# Sheet1.net
KiCad netlist of a schematic drawn in Altium Designer
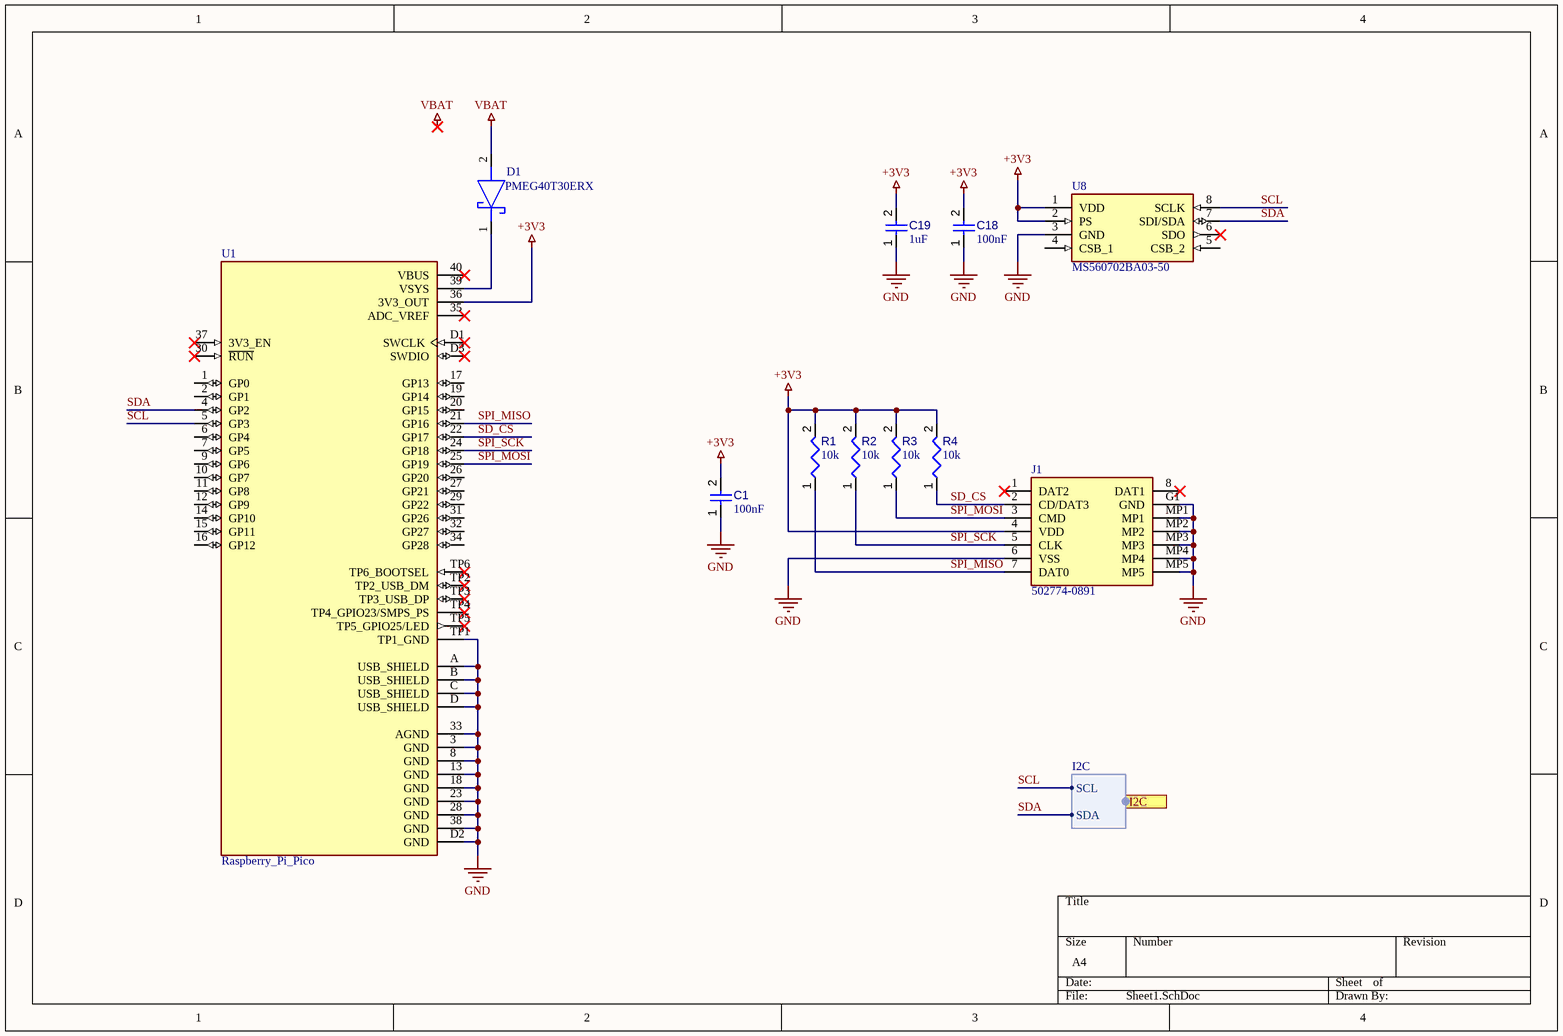
[diagram p0: Sheet1.SchDoc]

(export (version "E")
  (design (tool "Eeschema 10.0.6"))
  (components
    (comp (ref "C1")
      (value "100nF")
      (footprint "CAPC1608X90X40NL10T20")
      (description "Chip Capacitor, 100 nF, +/- 10%, 50 V, 0603 (1608 Metric)")
      (fields (field (name "TOLERANCE") "10%") (field (name "Comment") "Capacitor 100 nF +/-10% 50 V 0603"))
      (libsource (lib "PWr in Space team") (part "CAP-NP-2"))
    )
    (comp (ref "C18")
      (value "100nF")
      (footprint "CAPC1608X90X40NL10T20")
      (description "Chip Capacitor, 100 nF, +/- 10%, 50 V, 0603 (1608 Metric)")
      (fields (field (name "TOLERANCE") "10%") (field (name "Comment") "Capacitor 100 nF +/-10% 50 V 0603"))
      (libsource (lib "PWr in Space team") (part "CAP-NP-2"))
    )
    (comp (ref "C19")
      (value "1uF")
      (footprint "CAPC1608X90X40NL10T20")
      (description "Chip Capacitor, 100 nF, +/- 10%, 50 V, 0603 (1608 Metric)")
      (fields (field (name "TOLERANCE") "10%") (field (name "Comment") "Capacitor 100 nF +/-10% 50 V 0603"))
      (libsource (lib "PWr in Space team") (part "CAP-NP-2"))
    )
    (comp (ref "D1")
      (value "PMEG40T30ERX")
      (footprint "SamacSys:SODFL3517X110N")
      (description "Schottky Diode")
      (fields
        (field (name "MANUFACTURER_PART_NUMBER") "PMEG60T30ELRX")
        (field (name "MOUSER PART NUMBER") "771-PMEG60T30ELRX")
      )
      (libsource (lib "*") (part "PMEG60T30ELRX"))
    )
    (comp (ref "J1")
      (value "502774-0891")
      (footprint "SamacSys:5027740891")
      (description "Connector")
      (fields (field (name "MOUSER PART NUMBER") "538-502774-0891"))
      (libsource (lib "*") (part "502774-0891"))
    )
    (comp (ref "R1")
      (value "10k")
      (footprint "RESC1608X55X25ML10T15")
      (description "Chip Resistor, 10 KOhm, +/- 1%, 01 W, -55 to 155 degC, 0603 (1608 Metric)")
      (fields (field (name "POWER") "100mW") (field (name "TOLERANCE") "1%"))
      (libsource (lib "PWr in Space team") (part "RES-2"))
    )
    (comp (ref "R2")
      (value "10k")
      (footprint "RESC1608X55X25ML10T15")
      (description "Chip Resistor, 10 KOhm, +/- 1%, 01 W, -55 to 155 degC, 0603 (1608 Metric)")
      (fields (field (name "POWER") "100mW") (field (name "TOLERANCE") "1%"))
      (libsource (lib "PWr in Space team") (part "RES-2"))
    )
    (comp (ref "R3")
      (value "10k")
      (footprint "RESC1608X55X25ML10T15")
      (description "Chip Resistor, 10 KOhm, +/- 1%, 01 W, -55 to 155 degC, 0603 (1608 Metric)")
      (fields (field (name "POWER") "100mW") (field (name "TOLERANCE") "1%"))
      (libsource (lib "PWr in Space team") (part "RES-2"))
    )
    (comp (ref "R4")
      (value "10k")
      (footprint "RESC1608X55X25ML10T15")
      (description "Chip Resistor, 10 KOhm, +/- 1%, 01 W, -55 to 155 degC, 0603 (1608 Metric)")
      (fields (field (name "POWER") "100mW") (field (name "TOLERANCE") "1%"))
      (libsource (lib "PWr in Space team") (part "RES-2"))
    )
    (comp (ref "U1")
      (value "Raspberry_Pi_Pico")
      (footprint "MODULE_SC0915")
      (description "RP2040 Raspberry Pi Pico series ARMÂ® CortexÂ®-M0+ MCU 32-Bit Embedded Evaluation Board")
      (fields (field (name "MP") "SC0915") (field (name "MF") "Raspberry Pi"))
      (libsource (lib "PWr in Space team") (part "SC0915"))
    )
    (comp (ref "U8")
      (value "MS560702BA03-50")
      (footprint "SamacSys:MS5607-02BA03")
      (description "Integrated Circuit")
      (fields (field (name "MOUSER PART NUMBER") "824-MS560702BA03-50"))
      (libsource (lib "*") (part "MS560702BA03-50"))
    )
  )
  (nets
    (net (code "2") (name "+3V3") (class "Default")
      (node (ref "C1") (pin "2") (pinfunction "2_2") (pintype "passive"))
      (node (ref "C18") (pin "2") (pinfunction "2_2") (pintype "passive"))
      (node (ref "C19") (pin "2") (pinfunction "2_2") (pintype "passive"))
      (node (ref "J1") (pin "4") (pinfunction "VDD_4") (pintype "passive"))
      (node (ref "R1") (pin "2") (pinfunction "2_2") (pintype "passive"))
      (node (ref "R2") (pin "2") (pinfunction "2_2") (pintype "passive"))
      (node (ref "R3") (pin "2") (pinfunction "2_2") (pintype "passive"))
      (node (ref "R4") (pin "2") (pinfunction "2_2") (pintype "passive"))
      (node (ref "U1") (pin "36") (pinfunction "3V3_OUT_36") (pintype "power_in"))
      (node (ref "U8") (pin "1") (pinfunction "VDD_1") (pintype "power_in"))
      (node (ref "U8") (pin "2") (pinfunction "PS_2") (pintype "input"))
    )
    (net (code "3") (name "/SCL") (class "Default")
      (node (ref "U1") (pin "5") (pinfunction "GP3_5") (pintype "bidirectional"))
      (node (ref "U8") (pin "8") (pinfunction "SCLK_8") (pintype "input"))
    )
    (net (code "4") (name "/SDA") (class "Default")
      (node (ref "U1") (pin "4") (pinfunction "GP2_4") (pintype "bidirectional"))
      (node (ref "U8") (pin "7") (pinfunction "SDI/SDA_7") (pintype "bidirectional"))
    )
    (net (code "5") (name "/SD_CS") (class "Default")
      (node (ref "J1") (pin "2") (pinfunction "CD/DAT3_2") (pintype "passive"))
      (node (ref "R4") (pin "1") (pinfunction "1_1") (pintype "passive"))
      (node (ref "U1") (pin "22") (pinfunction "GP17_22") (pintype "bidirectional"))
    )
    (net (code "6") (name "/SPI_MISO") (class "Default")
      (node (ref "J1") (pin "7") (pinfunction "DAT0_7") (pintype "passive"))
      (node (ref "R1") (pin "1") (pinfunction "1_1") (pintype "passive"))
      (node (ref "U1") (pin "21") (pinfunction "GP16_21") (pintype "bidirectional"))
    )
    (net (code "7") (name "/SPI_MOSI") (class "Default")
      (node (ref "J1") (pin "3") (pinfunction "CMD_3") (pintype "passive"))
      (node (ref "R3") (pin "1") (pinfunction "1_1") (pintype "passive"))
      (node (ref "U1") (pin "25") (pinfunction "GP19_25") (pintype "bidirectional"))
    )
    (net (code "8") (name "/SPI_SCK") (class "Default")
      (node (ref "J1") (pin "5") (pinfunction "CLK_5") (pintype "passive"))
      (node (ref "R2") (pin "1") (pinfunction "1_1") (pintype "passive"))
      (node (ref "U1") (pin "24") (pinfunction "GP18_24") (pintype "bidirectional"))
    )
    (net (code "10") (name "GND") (class "Default")
      (node (ref "C1") (pin "1") (pinfunction "1_1") (pintype "passive"))
      (node (ref "C18") (pin "1") (pinfunction "1_1") (pintype "passive"))
      (node (ref "C19") (pin "1") (pinfunction "1_1") (pintype "passive"))
      (node (ref "J1") (pin "6") (pinfunction "VSS_6") (pintype "passive"))
      (node (ref "J1") (pin "G1") (pinfunction "GND_G1") (pintype "passive"))
      (node (ref "J1") (pin "MP1") (pinfunction "MP1_MP1") (pintype "passive"))
      (node (ref "J1") (pin "MP2") (pinfunction "MP2_MP2") (pintype "passive"))
      (node (ref "J1") (pin "MP3") (pinfunction "MP3_MP3") (pintype "passive"))
      (node (ref "J1") (pin "MP4") (pinfunction "MP4_MP4") (pintype "passive"))
      (node (ref "J1") (pin "MP5") (pinfunction "MP5_MP5") (pintype "passive"))
      (node (ref "U1") (pin "13") (pinfunction "GND_13") (pintype "power_in"))
      (node (ref "U1") (pin "18") (pinfunction "GND_18") (pintype "power_in"))
      (node (ref "U1") (pin "23") (pinfunction "GND_23") (pintype "power_in"))
      (node (ref "U1") (pin "28") (pinfunction "GND_28") (pintype "power_in"))
      (node (ref "U1") (pin "3") (pinfunction "GND_3") (pintype "power_in"))
      (node (ref "U1") (pin "33") (pinfunction "AGND_33") (pintype "power_in"))
      (node (ref "U1") (pin "38") (pinfunction "GND_38") (pintype "power_in"))
      (node (ref "U1") (pin "8") (pinfunction "GND_8") (pintype "power_in"))
      (node (ref "U1") (pin "A") (pinfunction "USB_SHIELD_A") (pintype "power_in"))
      (node (ref "U1") (pin "B") (pinfunction "USB_SHIELD_B") (pintype "power_in"))
      (node (ref "U1") (pin "C") (pinfunction "USB_SHIELD_C") (pintype "power_in"))
      (node (ref "U1") (pin "D") (pinfunction "USB_SHIELD_D") (pintype "power_in"))
      (node (ref "U1") (pin "D2") (pinfunction "GND_D2") (pintype "power_in"))
      (node (ref "U1") (pin "TP1") (pinfunction "TP1_GND_TP1") (pintype "power_in"))
      (node (ref "U8") (pin "3") (pinfunction "GND_3") (pintype "power_in"))
    )
    (net (code "11") (name "Net-(D1-K)") (class "Default")
      (node (ref "D1") (pin "1") (pinfunction "K_1") (pintype "passive"))
      (node (ref "U1") (pin "39") (pinfunction "VSYS_39") (pintype "power_in"))
    )
    (net (code "12") (name "VBAT") (class "Default")
      (node (ref "D1") (pin "2") (pinfunction "A_2") (pintype "passive"))
    )
    (net (code "13") (name "unconnected-(J1-DAT1-Pad8)") (class "Default")
      (node (ref "J1") (pin "8") (pinfunction "DAT1_8") (pintype "passive+no_connect"))
    )
    (net (code "14") (name "unconnected-(J1-DAT2-Pad1)") (class "Default")
      (node (ref "J1") (pin "1") (pinfunction "DAT2_1") (pintype "passive+no_connect"))
    )
    (net (code "15") (name "unconnected-(U1-3V3_EN-Pad37)") (class "Default")
      (node (ref "U1") (pin "37") (pinfunction "3V3_EN_37") (pintype "input+no_connect"))
    )
    (net (code "16") (name "unconnected-(U1-ADC_VREF-Pad35)") (class "Default")
      (node (ref "U1") (pin "35") (pinfunction "ADC_VREF_35") (pintype "power_in+no_connect"))
    )
    (net (code "17") (name "unconnected-(U1-GP0-Pad1)") (class "Default")
      (node (ref "U1") (pin "1") (pinfunction "GP0_1") (pintype "bidirectional"))
    )
    (net (code "18") (name "unconnected-(U1-GP1-Pad2)") (class "Default")
      (node (ref "U1") (pin "2") (pinfunction "GP1_2") (pintype "bidirectional"))
    )
    (net (code "19") (name "unconnected-(U1-GP4-Pad6)") (class "Default")
      (node (ref "U1") (pin "6") (pinfunction "GP4_6") (pintype "bidirectional"))
    )
    (net (code "20") (name "unconnected-(U1-GP5-Pad7)") (class "Default")
      (node (ref "U1") (pin "7") (pinfunction "GP5_7") (pintype "bidirectional"))
    )
    (net (code "21") (name "unconnected-(U1-GP6-Pad9)") (class "Default")
      (node (ref "U1") (pin "9") (pinfunction "GP6_9") (pintype "bidirectional"))
    )
    (net (code "22") (name "unconnected-(U1-GP7-Pad10)") (class "Default")
      (node (ref "U1") (pin "10") (pinfunction "GP7_10") (pintype "bidirectional"))
    )
    (net (code "23") (name "unconnected-(U1-GP8-Pad11)") (class "Default")
      (node (ref "U1") (pin "11") (pinfunction "GP8_11") (pintype "bidirectional"))
    )
    (net (code "24") (name "unconnected-(U1-GP9-Pad12)") (class "Default")
      (node (ref "U1") (pin "12") (pinfunction "GP9_12") (pintype "bidirectional"))
    )
    (net (code "25") (name "unconnected-(U1-GP10-Pad14)") (class "Default")
      (node (ref "U1") (pin "14") (pinfunction "GP10_14") (pintype "bidirectional"))
    )
    (net (code "26") (name "unconnected-(U1-GP11-Pad15)") (class "Default")
      (node (ref "U1") (pin "15") (pinfunction "GP11_15") (pintype "bidirectional"))
    )
    (net (code "27") (name "unconnected-(U1-GP12-Pad16)") (class "Default")
      (node (ref "U1") (pin "16") (pinfunction "GP12_16") (pintype "bidirectional"))
    )
    (net (code "28") (name "unconnected-(U1-GP13-Pad17)") (class "Default")
      (node (ref "U1") (pin "17") (pinfunction "GP13_17") (pintype "bidirectional"))
    )
    (net (code "29") (name "unconnected-(U1-GP14-Pad19)") (class "Default")
      (node (ref "U1") (pin "19") (pinfunction "GP14_19") (pintype "bidirectional"))
    )
    (net (code "30") (name "unconnected-(U1-GP15-Pad20)") (class "Default")
      (node (ref "U1") (pin "20") (pinfunction "GP15_20") (pintype "bidirectional"))
    )
    (net (code "31") (name "unconnected-(U1-GP20-Pad26)") (class "Default")
      (node (ref "U1") (pin "26") (pinfunction "GP20_26") (pintype "bidirectional"))
    )
    (net (code "32") (name "unconnected-(U1-GP21-Pad27)") (class "Default")
      (node (ref "U1") (pin "27") (pinfunction "GP21_27") (pintype "bidirectional"))
    )
    (net (code "33") (name "unconnected-(U1-GP22-Pad29)") (class "Default")
      (node (ref "U1") (pin "29") (pinfunction "GP22_29") (pintype "bidirectional"))
    )
    (net (code "34") (name "unconnected-(U1-GP26-Pad31)") (class "Default")
      (node (ref "U1") (pin "31") (pinfunction "GP26_31") (pintype "bidirectional"))
    )
    (net (code "35") (name "unconnected-(U1-GP27-Pad32)") (class "Default")
      (node (ref "U1") (pin "32") (pinfunction "GP27_32") (pintype "bidirectional"))
    )
    (net (code "36") (name "unconnected-(U1-GP28-Pad34)") (class "Default")
      (node (ref "U1") (pin "34") (pinfunction "GP28_34") (pintype "bidirectional"))
    )
    (net (code "37") (name "unconnected-(U1-SWCLK-PadD1)") (class "Default")
      (node (ref "U1") (pin "D1") (pinfunction "SWCLK_D1") (pintype "input+no_connect"))
    )
    (net (code "38") (name "unconnected-(U1-SWDIO-PadD3)") (class "Default")
      (node (ref "U1") (pin "D3") (pinfunction "SWDIO_D3") (pintype "bidirectional+no_connect"))
    )
    (net (code "39") (name "unconnected-(U1-TP2_USB_DM-PadTP2)") (class "Default")
      (node (ref "U1") (pin "TP2") (pinfunction "TP2_USB_DM_TP2") (pintype "bidirectional+no_connect"))
    )
    (net (code "40") (name "unconnected-(U1-TP3_USB_DP-PadTP3)") (class "Default")
      (node (ref "U1") (pin "TP3") (pinfunction "TP3_USB_DP_TP3") (pintype "bidirectional+no_connect"))
    )
    (net (code "41") (name "unconnected-(U1-TP4_GPIO23{slash}SMPS_PS-PadTP4)") (class "Default")
      (node (ref "U1") (pin "TP4") (pinfunction "TP4_GPIO23/SMPS_PS_TP4") (pintype "passive+no_connect"))
    )
    (net (code "42") (name "unconnected-(U1-TP5_GPIO25{slash}LED-PadTP5)") (class "Default")
      (node (ref "U1") (pin "TP5") (pinfunction "TP5_GPIO25/LED_TP5") (pintype "output+no_connect"))
    )
    (net (code "43") (name "unconnected-(U1-TP6_BOOTSEL-PadTP6)") (class "Default")
      (node (ref "U1") (pin "TP6") (pinfunction "TP6_BOOTSEL_TP6") (pintype "input+no_connect"))
    )
    (net (code "44") (name "unconnected-(U1-VBUS-Pad40)") (class "Default")
      (node (ref "U1") (pin "40") (pinfunction "VBUS_40") (pintype "power_in+no_connect"))
    )
    (net (code "45") (name "unconnected-(U1-~{RUN}-Pad30)") (class "Default")
      (node (ref "U1") (pin "30") (pinfunction "~{RUN}_30") (pintype "input+no_connect"))
    )
    (net (code "46") (name "unconnected-(U8-CSB_1-Pad4)") (class "Default")
      (node (ref "U8") (pin "4") (pinfunction "CSB_1_4") (pintype "input"))
    )
    (net (code "47") (name "unconnected-(U8-CSB_2-Pad5)") (class "Default")
      (node (ref "U8") (pin "5") (pinfunction "CSB_2_5") (pintype "input"))
    )
    (net (code "48") (name "unconnected-(U8-SDO-Pad6)") (class "Default")
      (node (ref "U8") (pin "6") (pinfunction "SDO_6") (pintype "output+no_connect"))
    )
  )
)
